# PISANG2.net
KiCad netlist of a schematic drawn in EAGLE
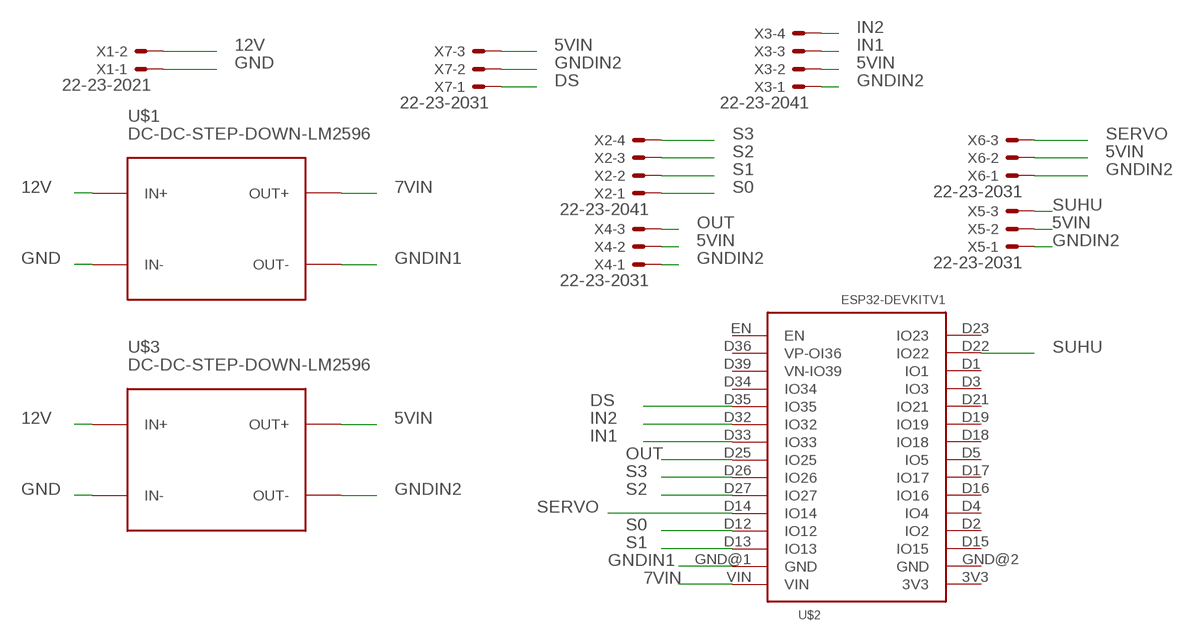
[diagram p0: schematic, sheet 1]

(export (version "E")
  (design (tool "Eeschema 10.0.6"))
  (components
    (comp (ref "U$1")
      (value "DC-DC-STEP-DOWN-LM2596")
      (footprint "eagle-import:DC-DC-STEP-DOWN-LM2596")
      (libsource (lib "eagle-import") (part "DC-DC-STEP-DOWN-LM2596"))
    )
    (comp (ref "U$2")
      (value "ESP32DEVKITV1")
      (footprint "eagle-import:ESP32-DEVKITV1")
      (libsource (lib "eagle-import") (part "ESP32DEVKITV1"))
    )
    (comp (ref "U$3")
      (value "DC-DC-STEP-DOWN-LM2596")
      (footprint "eagle-import:DC-DC-STEP-DOWN-LM2596")
      (libsource (lib "eagle-import") (part "DC-DC-STEP-DOWN-LM2596"))
    )
    (comp (ref "X1")
      (value "22-23-2021")
      (footprint "eagle-import:22-23-2021")
      (fields (field (name "MF") "MOLEX"))
      (libsource (lib "eagle-import") (part "22-23-2021"))
    )
    (comp (ref "X2")
      (value "22-23-2041")
      (footprint "eagle-import:22-23-2041")
      (fields (field (name "MF") "MOLEX"))
      (libsource (lib "eagle-import") (part "22-23-2041"))
    )
    (comp (ref "X3")
      (value "22-23-2041")
      (footprint "eagle-import:22-23-2041")
      (fields (field (name "MF") "MOLEX"))
      (libsource (lib "eagle-import") (part "22-23-2041"))
    )
    (comp (ref "X4")
      (value "22-23-2031")
      (footprint "eagle-import:22-23-2031")
      (fields (field (name "MF") "MOLEX"))
      (libsource (lib "eagle-import") (part "22-23-2031"))
    )
    (comp (ref "X5")
      (value "22-23-2031")
      (footprint "eagle-import:22-23-2031")
      (fields (field (name "MF") "MOLEX"))
      (libsource (lib "eagle-import") (part "22-23-2031"))
    )
    (comp (ref "X6")
      (value "22-23-2031")
      (footprint "eagle-import:22-23-2031")
      (fields (field (name "MF") "MOLEX"))
      (libsource (lib "eagle-import") (part "22-23-2031"))
    )
    (comp (ref "X7")
      (value "22-23-2031")
      (footprint "eagle-import:22-23-2031")
      (fields (field (name "MF") "MOLEX"))
      (libsource (lib "eagle-import") (part "22-23-2031"))
    )
  )
  (nets
    (net (code "1") (name "/5VIN") (class "Default")
      (node (ref "U$3") (pin "OUT+") (pinfunction "OUT+_OUT+") (pintype "bidirectional"))
      (node (ref "X3") (pin "2") (pinfunction "S_2") (pintype "passive"))
      (node (ref "X4") (pin "2") (pinfunction "S_2") (pintype "passive"))
      (node (ref "X5") (pin "2") (pinfunction "S_2") (pintype "passive"))
      (node (ref "X6") (pin "2") (pinfunction "S_2") (pintype "passive"))
      (node (ref "X7") (pin "3") (pinfunction "S_3") (pintype "passive"))
    )
    (net (code "2") (name "/7VIN") (class "Default")
      (node (ref "U$1") (pin "OUT+") (pinfunction "OUT+_OUT+") (pintype "bidirectional"))
      (node (ref "U$2") (pin "VIN") (pinfunction "VIN_VIN") (pintype "bidirectional"))
    )
    (net (code "3") (name "/12V") (class "Default")
      (node (ref "U$1") (pin "IN+") (pinfunction "IN+_IN+") (pintype "bidirectional"))
      (node (ref "U$3") (pin "IN+") (pinfunction "IN+_IN+") (pintype "bidirectional"))
      (node (ref "X1") (pin "2") (pinfunction "S_2") (pintype "passive"))
    )
    (net (code "4") (name "/DS") (class "Default")
      (node (ref "U$2") (pin "D35") (pinfunction "IO35_D35") (pintype "bidirectional"))
      (node (ref "X7") (pin "1") (pinfunction "S_1") (pintype "passive"))
    )
    (net (code "5") (name "/GND") (class "Default")
      (node (ref "U$1") (pin "IN-") (pinfunction "IN-_IN-") (pintype "bidirectional"))
      (node (ref "U$3") (pin "IN-") (pinfunction "IN-_IN-") (pintype "bidirectional"))
      (node (ref "X1") (pin "1") (pinfunction "S_1") (pintype "passive"))
    )
    (net (code "6") (name "/GNDIN1") (class "Default")
      (node (ref "U$1") (pin "OUT-") (pinfunction "OUT-_OUT-") (pintype "bidirectional"))
      (node (ref "U$2") (pin "GND@1") (pinfunction "GND_GND@1") (pintype "bidirectional"))
    )
    (net (code "7") (name "/GNDIN2") (class "Default")
      (node (ref "U$3") (pin "OUT-") (pinfunction "OUT-_OUT-") (pintype "bidirectional"))
      (node (ref "X3") (pin "1") (pinfunction "S_1") (pintype "passive"))
      (node (ref "X4") (pin "1") (pinfunction "S_1") (pintype "passive"))
      (node (ref "X5") (pin "1") (pinfunction "S_1") (pintype "passive"))
      (node (ref "X6") (pin "1") (pinfunction "S_1") (pintype "passive"))
      (node (ref "X7") (pin "2") (pinfunction "S_2") (pintype "passive"))
    )
    (net (code "8") (name "/IN1") (class "Default")
      (node (ref "U$2") (pin "D33") (pinfunction "IO33_D33") (pintype "bidirectional"))
      (node (ref "X3") (pin "3") (pinfunction "S_3") (pintype "passive"))
    )
    (net (code "9") (name "/IN2") (class "Default")
      (node (ref "U$2") (pin "D32") (pinfunction "IO32_D32") (pintype "bidirectional"))
      (node (ref "X3") (pin "4") (pinfunction "S_4") (pintype "passive"))
    )
    (net (code "10") (name "/OUT") (class "Default")
      (node (ref "U$2") (pin "D25") (pinfunction "IO25_D25") (pintype "bidirectional"))
      (node (ref "X4") (pin "3") (pinfunction "S_3") (pintype "passive"))
    )
    (net (code "11") (name "/S0") (class "Default")
      (node (ref "U$2") (pin "D12") (pinfunction "IO12_D12") (pintype "bidirectional"))
      (node (ref "X2") (pin "1") (pinfunction "S_1") (pintype "passive"))
    )
    (net (code "12") (name "/S1") (class "Default")
      (node (ref "U$2") (pin "D13") (pinfunction "IO13_D13") (pintype "bidirectional"))
      (node (ref "X2") (pin "2") (pinfunction "S_2") (pintype "passive"))
    )
    (net (code "13") (name "/S2") (class "Default")
      (node (ref "U$2") (pin "D27") (pinfunction "IO27_D27") (pintype "bidirectional"))
      (node (ref "X2") (pin "3") (pinfunction "S_3") (pintype "passive"))
    )
    (net (code "14") (name "/S3") (class "Default")
      (node (ref "U$2") (pin "D26") (pinfunction "IO26_D26") (pintype "bidirectional"))
      (node (ref "X2") (pin "4") (pinfunction "S_4") (pintype "passive"))
    )
    (net (code "15") (name "/SERVO") (class "Default")
      (node (ref "U$2") (pin "D14") (pinfunction "IO14_D14") (pintype "bidirectional"))
      (node (ref "X6") (pin "3") (pinfunction "S_3") (pintype "passive"))
    )
    (net (code "16") (name "/SUHU") (class "Default")
      (node (ref "U$2") (pin "D22") (pinfunction "IO22_D22") (pintype "bidirectional"))
      (node (ref "X5") (pin "3") (pinfunction "S_3") (pintype "passive"))
    )
    (net (code "17") (name "unconnected-(U$2-GND-PadGND@2)") (class "Default")
      (node (ref "U$2") (pin "GND@2") (pinfunction "GND_GND@2") (pintype "bidirectional"))
    )
    (net (code "18") (name "unconnected-(U$2-IO1-PadD1)") (class "Default")
      (node (ref "U$2") (pin "D1") (pinfunction "IO1_D1") (pintype "bidirectional"))
    )
    (net (code "19") (name "unconnected-(U$2-IO2-PadD2)") (class "Default")
      (node (ref "U$2") (pin "D2") (pinfunction "IO2_D2") (pintype "bidirectional"))
    )
    (net (code "20") (name "unconnected-(U$2-IO3-PadD3)") (class "Default")
      (node (ref "U$2") (pin "D3") (pinfunction "IO3_D3") (pintype "bidirectional"))
    )
    (net (code "21") (name "unconnected-(U$2-IO4-PadD4)") (class "Default")
      (node (ref "U$2") (pin "D4") (pinfunction "IO4_D4") (pintype "bidirectional"))
    )
    (net (code "22") (name "unconnected-(U$2-IO5-PadD5)") (class "Default")
      (node (ref "U$2") (pin "D5") (pinfunction "IO5_D5") (pintype "bidirectional"))
    )
    (net (code "23") (name "unconnected-(U$2-IO15-PadD15)") (class "Default")
      (node (ref "U$2") (pin "D15") (pinfunction "IO15_D15") (pintype "bidirectional"))
    )
    (net (code "24") (name "unconnected-(U$2-IO16-PadD16)") (class "Default")
      (node (ref "U$2") (pin "D16") (pinfunction "IO16_D16") (pintype "bidirectional"))
    )
    (net (code "25") (name "unconnected-(U$2-IO17-PadD17)") (class "Default")
      (node (ref "U$2") (pin "D17") (pinfunction "IO17_D17") (pintype "bidirectional"))
    )
    (net (code "26") (name "unconnected-(U$2-IO18-PadD18)") (class "Default")
      (node (ref "U$2") (pin "D18") (pinfunction "IO18_D18") (pintype "bidirectional"))
    )
    (net (code "27") (name "unconnected-(U$2-IO19-PadD19)") (class "Default")
      (node (ref "U$2") (pin "D19") (pinfunction "IO19_D19") (pintype "bidirectional"))
    )
    (net (code "28") (name "unconnected-(U$2-IO21-PadD21)") (class "Default")
      (node (ref "U$2") (pin "D21") (pinfunction "IO21_D21") (pintype "bidirectional"))
    )
    (net (code "29") (name "unconnected-(U$2-IO23-PadD23)") (class "Default")
      (node (ref "U$2") (pin "D23") (pinfunction "IO23_D23") (pintype "bidirectional"))
    )
    (net (code "30") (name "unconnected-(U$2-IO34-PadD34)") (class "Default")
      (node (ref "U$2") (pin "D34") (pinfunction "IO34_D34") (pintype "bidirectional"))
    )
    (net (code "31") (name "unconnected-(U$2-Pad3V3)") (class "Default")
      (node (ref "U$2") (pin "3V3") (pinfunction "3V3_3V3") (pintype "bidirectional"))
    )
    (net (code "32") (name "unconnected-(U$2-PadEN)") (class "Default")
      (node (ref "U$2") (pin "EN") (pinfunction "EN_EN") (pintype "bidirectional"))
    )
    (net (code "33") (name "unconnected-(U$2-VN-IO39-PadD39)") (class "Default")
      (node (ref "U$2") (pin "D39") (pinfunction "VN-IO39_D39") (pintype "bidirectional"))
    )
    (net (code "34") (name "unconnected-(U$2-VP-OI36-PadD36)") (class "Default")
      (node (ref "U$2") (pin "D36") (pinfunction "VP-OI36_D36") (pintype "bidirectional"))
    )
  )
)
